# analog_channel.net
KiCad netlist of a schematic drawn in Altium Designer
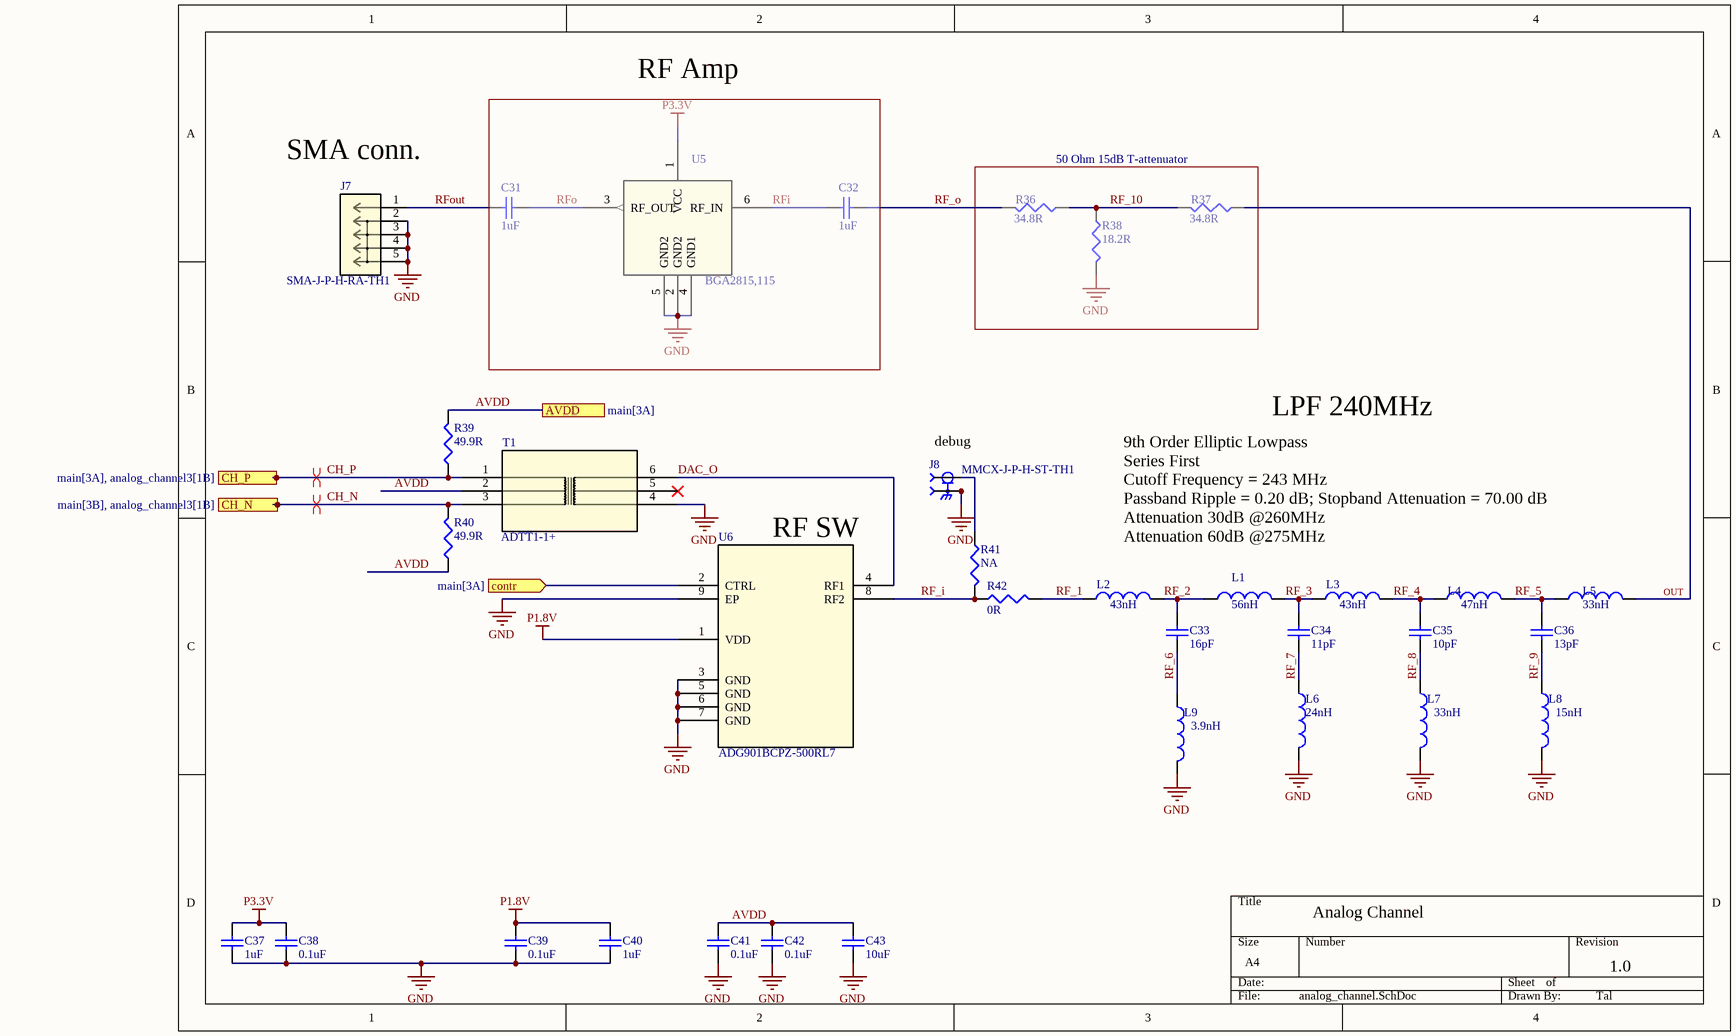
[diagram p0: analog_channel.SchDoc]

(export (version "E")
  (design (tool "Eeschema 10.0.6"))
  (components
    (comp (ref "C31")
      (value "1uF 25V")
      (footprint "Landa_PCB:C0402")
      (description "CAP CER 1uF 25V X5R 0402")
      (fields
        (field (name "MANUFACTURER PART NUMBER") "C1005C0G1H6R8D")
        (field (name "MANUFACTURER") "TDK Corporation")
        (field (name "CAPACITANCE") "1uF")
      )
      (libsource (lib "L_SCH_C") (part "CAP CER 6.8pF 50V NP0 0402"))
    )
    (comp (ref "C32")
      (value "1uF 25V")
      (footprint "Landa_PCB:C0402")
      (description "CAP CER 1uF 25V X5R 0402")
      (fields
        (field (name "MANUFACTURER PART NUMBER") "C1005C0G1H6R8D")
        (field (name "MANUFACTURER") "TDK Corporation")
        (field (name "CAPACITANCE") "1uF")
      )
      (libsource (lib "L_SCH_C") (part "CAP CER 6.8pF 50V NP0 0402"))
    )
    (comp (ref "C33")
      (value "16pF 50V")
      (footprint "Landa_PCB:C0402")
      (description "CAP CER 16PF 50V 5% NP0 0402")
      (fields
        (field (name "MANUFACTURER") "TDK Corporation")
        (field (name "MANUFACTURER PART NUMBER") "C1005C0G1H200J")
        (field (name "CAPACITANCE") "16pF")
      )
      (libsource (lib "L_SCH_C") (part "CAP CER 20pF 50V 5% NP0 0402"))
    )
    (comp (ref "C34")
      (value "11pF 50V")
      (footprint "Landa_PCB:C0402")
      (description "CAP CER 11PF 50V 5% NP0 0402")
      (fields
        (field (name "MANUFACTURER") "TDK Corporation")
        (field (name "MANUFACTURER PART NUMBER") "C1005C0G1H200J")
        (field (name "CAPACITANCE") "11pF")
      )
      (libsource (lib "L_SCH_C") (part "CAP CER 20pF 50V 5% NP0 0402"))
    )
    (comp (ref "C35")
      (value "10pF 50V")
      (footprint "Landa_PCB:C0402")
      (description "CAP CER 10PF 50V 5% NP0 0402")
      (fields
        (field (name "MANUFACTURER") "TDK Corporation")
        (field (name "MANUFACTURER PART NUMBER") "C1005C0G1H200J")
        (field (name "CAPACITANCE") "10pF")
      )
      (libsource (lib "L_SCH_C") (part "CAP CER 20pF 50V 5% NP0 0402"))
    )
    (comp (ref "C36")
      (value "13pF 50V")
      (footprint "Landa_PCB:C0402")
      (description "CAP CER 13PF 50V 5% NP0 0402")
      (fields
        (field (name "MANUFACTURER") "TDK Corporation")
        (field (name "MANUFACTURER PART NUMBER") "C1005C0G1H200J")
        (field (name "CAPACITANCE") "13pF")
      )
      (libsource (lib "L_SCH_C") (part "CAP CER 20pF 50V 5% NP0 0402"))
    )
    (comp (ref "C37")
      (value "1uF 25V")
      (footprint "Landa_PCB:C0402")
      (description "CAP CER 1uF 25V X5R 0402")
      (fields
        (field (name "MANUFACTURER PART NUMBER") "C1005C0G1H6R8D")
        (field (name "MANUFACTURER") "TDK Corporation")
        (field (name "CAPACITANCE") "1uF")
      )
      (libsource (lib "L_SCH_C") (part "CAP CER 6.8pF 50V NP0 0402"))
    )
    (comp (ref "C38")
      (value "0.1uF 50V")
      (footprint "Landa_PCB:C0402")
      (description "CAP CER 0.1uF 50V NP0 0402")
      (fields
        (field (name "MANUFACTURER PART NUMBER") "C1005C0G1H6R8D")
        (field (name "MANUFACTURER") "TDK Corporation")
        (field (name "CAPACITANCE") "0.1uF")
      )
      (libsource (lib "L_SCH_C") (part "CAP CER 6.8pF 50V NP0 0402"))
    )
    (comp (ref "C39")
      (value "0.1uF 50V")
      (footprint "Landa_PCB:C0402")
      (description "CAP CER 0.1uF 50V NP0 0402")
      (fields
        (field (name "MANUFACTURER PART NUMBER") "C1005C0G1H6R8D")
        (field (name "MANUFACTURER") "TDK Corporation")
        (field (name "CAPACITANCE") "0.1uF")
      )
      (libsource (lib "L_SCH_C") (part "CAP CER 6.8pF 50V NP0 0402"))
    )
    (comp (ref "C40")
      (value "1uF 25V")
      (footprint "Landa_PCB:C0402")
      (description "CAP CER 1uF 25V X5R 0402")
      (fields
        (field (name "MANUFACTURER PART NUMBER") "C1005C0G1H6R8D")
        (field (name "MANUFACTURER") "TDK Corporation")
        (field (name "CAPACITANCE") "1uF")
      )
      (libsource (lib "L_SCH_C") (part "CAP CER 6.8pF 50V NP0 0402"))
    )
    (comp (ref "C41")
      (value "0.1uF 50V")
      (footprint "Landa_PCB:C0402")
      (description "CAP CER 0.1uF 50V NP0 0402")
      (fields
        (field (name "MANUFACTURER PART NUMBER") "C1005C0G1H6R8D")
        (field (name "MANUFACTURER") "TDK Corporation")
        (field (name "CAPACITANCE") "0.1uF")
      )
      (libsource (lib "L_SCH_C") (part "CAP CER 6.8pF 50V NP0 0402"))
    )
    (comp (ref "C42")
      (value "0.1uF 50V")
      (footprint "Landa_PCB:C0402")
      (description "CAP CER 0.1uF 50V NP0 0402")
      (fields
        (field (name "MANUFACTURER PART NUMBER") "C1005C0G1H6R8D")
        (field (name "MANUFACTURER") "TDK Corporation")
        (field (name "CAPACITANCE") "0.1uF")
      )
      (libsource (lib "L_SCH_C") (part "CAP CER 6.8pF 50V NP0 0402"))
    )
    (comp (ref "C43")
      (value "10uF 10V")
      (footprint "Landa_PCB:C0402")
      (description "CAP CER 10uF 10V X5R 0402")
      (fields
        (field (name "MANUFACTURER PART NUMBER") "C1005C0G1H6R8D")
        (field (name "MANUFACTURER") "TDK Corporation")
        (field (name "CAPACITANCE") "10uF")
      )
      (libsource (lib "L_SCH_C") (part "CAP CER 6.8pF 50V NP0 0402"))
    )
    (comp (ref "J7")
      (value "SMA-J-P-H-RA-TH1")
      (footprint "CONN_SMA-J-P-H-RA-TH1_SAI")
      (description "No Description Available")
      (fields (field (name "COPYRIGHT") "Copyright (C) 2023 Ultra Librarian. All rights reserved."))
      (libsource (lib "SMA-J-P-H-RA-TH1") (part "SMA-J-P-H-RA-TH1"))
    )
    (comp (ref "J8")
      (value "MMCX-J-P-H-ST-TH1")
      (footprint "SAMTEC_MMCX-J-P-H-ST-TH1")
      (description "MMCX STRAIGHT, THROUGH HOLE JACK- 50 OHM")
      (fields (field (name "MF") "Samtec"))
      (libsource (lib "MMCX-J-P-H-ST-TH1") (part "MMCX-J-P-H-ST-TH1"))
    )
    (comp (ref "L1")
      (value "56nH")
      (footprint "0402-A")
      (description "Inductor")
      (fields (field (name "PUBLISHER") "Altium Limited"))
      (libsource (lib "Miscellaneous Devices") (part "Inductor"))
    )
    (comp (ref "L2")
      (value "43nH")
      (footprint "0402-A")
      (description "Inductor")
      (fields (field (name "PUBLISHER") "Altium Limited"))
      (libsource (lib "Miscellaneous Devices") (part "Inductor"))
    )
    (comp (ref "L3")
      (value "43nH")
      (footprint "0402-A")
      (description "Inductor")
      (fields (field (name "PUBLISHER") "Altium Limited"))
      (libsource (lib "Miscellaneous Devices") (part "Inductor"))
    )
    (comp (ref "L4")
      (value "47nH")
      (footprint "0402-A")
      (description "Inductor")
      (fields (field (name "PUBLISHER") "Altium Limited"))
      (libsource (lib "Miscellaneous Devices") (part "Inductor"))
    )
    (comp (ref "L5")
      (value "33nH")
      (footprint "0402-A")
      (description "Inductor")
      (fields (field (name "PUBLISHER") "Altium Limited"))
      (libsource (lib "Miscellaneous Devices") (part "Inductor"))
    )
    (comp (ref "L6")
      (value "24nH")
      (footprint "0402-A")
      (description "Inductor")
      (fields (field (name "PUBLISHER") "Altium Limited"))
      (libsource (lib "Miscellaneous Devices") (part "Inductor"))
    )
    (comp (ref "L7")
      (value "33nH")
      (footprint "0402-A")
      (description "Inductor")
      (fields (field (name "PUBLISHER") "Altium Limited"))
      (libsource (lib "Miscellaneous Devices") (part "Inductor"))
    )
    (comp (ref "L8")
      (value "15nH")
      (footprint "0402-A")
      (description "Inductor")
      (fields (field (name "PUBLISHER") "Altium Limited"))
      (libsource (lib "Miscellaneous Devices") (part "Inductor"))
    )
    (comp (ref "L9")
      (value "3.9nH")
      (footprint "0402-A")
      (description "Inductor")
      (fields (field (name "PUBLISHER") "Altium Limited"))
      (libsource (lib "Miscellaneous Devices") (part "Inductor"))
    )
    (comp (ref "R36")
      (value "34.8R")
      (footprint "r0402")
      (description "RES 34.8 OHM 1/10W 1% 0402 SMD")
      (fields
        (field (name "MANUFACTURER PART NUMBER") "ERJ-2RKF1000X")
        (field (name "MANUFACTURER") "Panasonic Electronic Components")
      )
      (libsource (lib "L_SCH_R") (part "RES 100 OHM 1/10W 1% 0402 SMD"))
    )
    (comp (ref "R37")
      (value "34.8R")
      (footprint "r0402")
      (description "RES 34.8 OHM 1/10W 1% 0402 SMD")
      (fields
        (field (name "MANUFACTURER PART NUMBER") "ERJ-2RKF1000X")
        (field (name "MANUFACTURER") "Panasonic Electronic Components")
      )
      (libsource (lib "L_SCH_R") (part "RES 100 OHM 1/10W 1% 0402 SMD"))
    )
    (comp (ref "R38")
      (value "18.2R")
      (footprint "r0402")
      (description "RES 18.2 OHM 1/10W 1% 0402 SMD")
      (fields
        (field (name "MANUFACTURER PART NUMBER") "ERJ-2RKF1000X")
        (field (name "MANUFACTURER") "Panasonic Electronic Components")
      )
      (libsource (lib "L_SCH_R") (part "RES 100 OHM 1/10W 1% 0402 SMD"))
    )
    (comp (ref "R39")
      (value "49.9R")
      (footprint "Landa_PCB:R0402")
      (description "RES 49.9 OHM 1/10W 1% 0402 SMD")
      (fields
        (field (name "MANUFACTURER PART NUMBER") "ERJ-2RKF1000X")
        (field (name "MANUFACTURER") "Panasonic Electronic Components")
      )
      (libsource (lib "L_SCH_R") (part "RES 100 OHM 1/10W 1% 0402 SMD"))
    )
    (comp (ref "R40")
      (value "49.9R")
      (footprint "Landa_PCB:R0402")
      (description "RES 49.9 OHM 1/10W 1% 0402 SMD")
      (fields
        (field (name "MANUFACTURER PART NUMBER") "ERJ-2RKF1000X")
        (field (name "MANUFACTURER") "Panasonic Electronic Components")
      )
      (libsource (lib "L_SCH_R") (part "RES 100 OHM 1/10W 1% 0402 SMD"))
    )
    (comp (ref "R41")
      (value "NA")
      (footprint "r0402")
      (description "RES 0 OHM 1/10W 1% 0402 SMD")
      (fields
        (field (name "MANUFACTURER PART NUMBER") "ERJ-2RKF1000X")
        (field (name "MANUFACTURER") "Panasonic Electronic Components")
      )
      (libsource (lib "L_SCH_R") (part "RES 100 OHM 1/10W 1% 0402 SMD"))
    )
    (comp (ref "R42")
      (value "0R")
      (footprint "r0402")
      (description "RES 0 OHM 1/10W 1% 0402 SMD")
      (fields
        (field (name "MANUFACTURER PART NUMBER") "ERJ-2RKF1000X")
        (field (name "MANUFACTURER") "Panasonic Electronic Components")
      )
      (libsource (lib "L_SCH_R") (part "RES 100 OHM 1/10W 1% 0402 SMD"))
    )
    (comp (ref "T1")
      (value "ADTT1-1+")
      (footprint "CD542_MNC")
      (description "No Description Available")
      (fields (field (name "COPYRIGHT") "Copyright (C) 2023 Ultra Librarian. All rights reserved."))
      (libsource (lib "ADTT1-1&plus_") (part "ADTT1-1+"))
    )
    (comp (ref "U5")
      (value "BGA2815,115")
      (footprint "SOT_2815,115_NXP")
      (description "No Description Available")
      (fields (field (name "COPYRIGHT") "Copyright (C) 2023 Ultra Librarian. All rights reserved."))
      (libsource (lib "BGA2815,115") (part "BGA2815,115"))
    )
    (comp (ref "U6")
      (value "ADG901BCPZ-500RL7")
      (footprint "CP_8_2_ADI")
      (description "No Description Available")
      (fields (field (name "COPYRIGHT") "Copyright (C) 2023 Ultra Librarian. All rights reserved."))
      (libsource (lib "ADG901BCPZ-500RL7") (part "ADG901BCPZ-500RL7"))
    )
  )
  (nets
    (net (code "1") (name "/AVDD") (class "Default")
      (node (ref "C41") (pin "2") (pinfunction "2_2") (pintype "passive"))
      (node (ref "C42") (pin "2") (pinfunction "2_2") (pintype "passive"))
      (node (ref "C43") (pin "2") (pinfunction "2_2") (pintype "passive"))
      (node (ref "R39") (pin "2") (pinfunction "2_2") (pintype "passive"))
      (node (ref "R40") (pin "1") (pinfunction "1_1") (pintype "passive"))
      (node (ref "T1") (pin "2") (pinfunction "2_2") (pintype "passive"))
    )
    (net (code "2") (name "/CH_N") (class "Default")
      (node (ref "R40") (pin "2") (pinfunction "2_2") (pintype "passive"))
      (node (ref "T1") (pin "3") (pinfunction "3_3") (pintype "passive"))
    )
    (net (code "3") (name "/CH_P") (class "Default")
      (node (ref "R39") (pin "1") (pinfunction "1_1") (pintype "passive"))
      (node (ref "T1") (pin "1") (pinfunction "1_1") (pintype "passive"))
    )
    (net (code "4") (name "/DAC_O") (class "Default")
      (node (ref "T1") (pin "6") (pinfunction "6_6") (pintype "passive"))
      (node (ref "U6") (pin "4") (pinfunction "RF1_4") (pintype "passive"))
    )
    (net (code "5") (name "/OUT") (class "Default")
      (node (ref "L5") (pin "2") (pinfunction "2_2") (pintype "passive"))
      (node (ref "R37") (pin "1") (pinfunction "1_1") (pintype "passive"))
    )
    (net (code "6") (name "/RF_1") (class "Default")
      (node (ref "L2") (pin "1") (pinfunction "1_1") (pintype "passive"))
      (node (ref "R42") (pin "2") (pinfunction "2_2") (pintype "passive"))
    )
    (net (code "7") (name "/RF_2") (class "Default")
      (node (ref "C33") (pin "1") (pinfunction "1_1") (pintype "passive"))
      (node (ref "L1") (pin "1") (pinfunction "1_1") (pintype "passive"))
      (node (ref "L2") (pin "2") (pinfunction "2_2") (pintype "passive"))
    )
    (net (code "8") (name "/RF_3") (class "Default")
      (node (ref "C34") (pin "1") (pinfunction "1_1") (pintype "passive"))
      (node (ref "L1") (pin "2") (pinfunction "2_2") (pintype "passive"))
      (node (ref "L3") (pin "1") (pinfunction "1_1") (pintype "passive"))
    )
    (net (code "9") (name "/RF_4") (class "Default")
      (node (ref "C35") (pin "1") (pinfunction "1_1") (pintype "passive"))
      (node (ref "L3") (pin "2") (pinfunction "2_2") (pintype "passive"))
      (node (ref "L4") (pin "1") (pinfunction "1_1") (pintype "passive"))
    )
    (net (code "10") (name "/RF_5") (class "Default")
      (node (ref "C36") (pin "1") (pinfunction "1_1") (pintype "passive"))
      (node (ref "L4") (pin "2") (pinfunction "2_2") (pintype "passive"))
      (node (ref "L5") (pin "1") (pinfunction "1_1") (pintype "passive"))
    )
    (net (code "11") (name "/RF_6") (class "Default")
      (node (ref "C33") (pin "2") (pinfunction "2_2") (pintype "passive"))
      (node (ref "L9") (pin "1") (pinfunction "1_1") (pintype "passive"))
    )
    (net (code "12") (name "/RF_7") (class "Default")
      (node (ref "C34") (pin "2") (pinfunction "2_2") (pintype "passive"))
      (node (ref "L6") (pin "1") (pinfunction "1_1") (pintype "passive"))
    )
    (net (code "13") (name "/RF_8") (class "Default")
      (node (ref "C35") (pin "2") (pinfunction "2_2") (pintype "passive"))
      (node (ref "L7") (pin "1") (pinfunction "1_1") (pintype "passive"))
    )
    (net (code "14") (name "/RF_9") (class "Default")
      (node (ref "C36") (pin "2") (pinfunction "2_2") (pintype "passive"))
      (node (ref "L8") (pin "1") (pinfunction "1_1") (pintype "passive"))
    )
    (net (code "15") (name "/RF_10") (class "Default")
      (node (ref "R36") (pin "1") (pinfunction "1_1") (pintype "passive"))
      (node (ref "R37") (pin "2") (pinfunction "2_2") (pintype "passive"))
      (node (ref "R38") (pin "1") (pinfunction "1_1") (pintype "passive"))
    )
    (net (code "16") (name "/RF_i") (class "Default")
      (node (ref "R41") (pin "2") (pinfunction "2_2") (pintype "passive"))
      (node (ref "R42") (pin "1") (pinfunction "1_1") (pintype "passive"))
      (node (ref "U6") (pin "8") (pinfunction "RF2_8") (pintype "passive"))
    )
    (net (code "17") (name "/RF_o") (class "Default")
      (node (ref "C32") (pin "2") (pinfunction "2_2") (pintype "passive"))
      (node (ref "R36") (pin "2") (pinfunction "2_2") (pintype "passive"))
    )
    (net (code "18") (name "/RFi") (class "Default")
      (node (ref "C32") (pin "1") (pinfunction "1_1") (pintype "passive"))
      (node (ref "U5") (pin "6") (pinfunction "RF_IN_6") (pintype "passive"))
    )
    (net (code "19") (name "/RFo") (class "Default")
      (node (ref "C31") (pin "2") (pinfunction "2_2") (pintype "passive"))
      (node (ref "U5") (pin "3") (pinfunction "RF_OUT_3") (pintype "output"))
    )
    (net (code "20") (name "/RFout") (class "Default")
      (node (ref "C31") (pin "1") (pinfunction "1_1") (pintype "passive"))
      (node (ref "J7") (pin "1") (pinfunction "1_1") (pintype "passive"))
    )
    (net (code "21") (name "/contr") (class "Default")
      (node (ref "U6") (pin "2") (pinfunction "CTRL_2") (pintype "passive"))
    )
    (net (code "22") (name "GND") (class "Default")
      (node (ref "C37") (pin "1") (pinfunction "1_1") (pintype "passive"))
      (node (ref "C38") (pin "1") (pinfunction "1_1") (pintype "passive"))
      (node (ref "C39") (pin "1") (pinfunction "1_1") (pintype "passive"))
      (node (ref "C40") (pin "1") (pinfunction "1_1") (pintype "passive"))
      (node (ref "C41") (pin "1") (pinfunction "1_1") (pintype "passive"))
      (node (ref "C42") (pin "1") (pinfunction "1_1") (pintype "passive"))
      (node (ref "C43") (pin "1") (pinfunction "1_1") (pintype "passive"))
      (node (ref "J7") (pin "2") (pinfunction "2_2") (pintype "passive"))
      (node (ref "J7") (pin "3") (pinfunction "3_3") (pintype "passive"))
      (node (ref "J7") (pin "4") (pinfunction "4_4") (pintype "passive"))
      (node (ref "J7") (pin "5") (pinfunction "5_5") (pintype "passive"))
      (node (ref "J8") (pin "S1") (pinfunction "2_S1") (pintype "passive"))
      (node (ref "J8") (pin "S2") (pinfunction "2_S2") (pintype "passive"))
      (node (ref "J8") (pin "S3") (pinfunction "2_S3") (pintype "passive"))
      (node (ref "J8") (pin "S4") (pinfunction "2_S4") (pintype "passive"))
      (node (ref "L6") (pin "2") (pinfunction "2_2") (pintype "passive"))
      (node (ref "L7") (pin "2") (pinfunction "2_2") (pintype "passive"))
      (node (ref "L8") (pin "2") (pinfunction "2_2") (pintype "passive"))
      (node (ref "L9") (pin "2") (pinfunction "2_2") (pintype "passive"))
      (node (ref "R38") (pin "2") (pinfunction "2_2") (pintype "passive"))
      (node (ref "T1") (pin "4") (pinfunction "4_4") (pintype "passive"))
      (node (ref "U5") (pin "2") (pinfunction "GND2_2") (pintype "passive"))
      (node (ref "U5") (pin "4") (pinfunction "GND1_4") (pintype "passive"))
      (node (ref "U5") (pin "5") (pinfunction "GND2_5") (pintype "passive"))
      (node (ref "U6") (pin "3") (pinfunction "GND_3") (pintype "passive"))
      (node (ref "U6") (pin "5") (pinfunction "GND_5") (pintype "passive"))
      (node (ref "U6") (pin "6") (pinfunction "GND_6") (pintype "passive"))
      (node (ref "U6") (pin "7") (pinfunction "GND_7") (pintype "passive"))
      (node (ref "U6") (pin "9") (pinfunction "EP_9") (pintype "passive"))
    )
    (net (code "23") (name "Net-(J8-Pad1)") (class "Default")
      (node (ref "J8") (pin "1") (pinfunction "1_1") (pintype "passive"))
      (node (ref "R41") (pin "1") (pinfunction "1_1") (pintype "passive"))
    )
    (net (code "24") (name "P1.8V") (class "Default")
      (node (ref "C39") (pin "2") (pinfunction "2_2") (pintype "passive"))
      (node (ref "C40") (pin "2") (pinfunction "2_2") (pintype "passive"))
      (node (ref "U6") (pin "1") (pinfunction "VDD_1") (pintype "power_in"))
    )
    (net (code "25") (name "P3.3V") (class "Default")
      (node (ref "C37") (pin "2") (pinfunction "2_2") (pintype "passive"))
      (node (ref "C38") (pin "2") (pinfunction "2_2") (pintype "passive"))
      (node (ref "U5") (pin "1") (pinfunction "VCC_1") (pintype "power_in"))
    )
    (net (code "26") (name "unconnected-(T1-Pad5)") (class "Default")
      (node (ref "T1") (pin "5") (pinfunction "5_5") (pintype "passive+no_connect"))
    )
  )
)
